# 4_PowerSupplie.net
KiCad netlist of a schematic drawn in Altium Designer
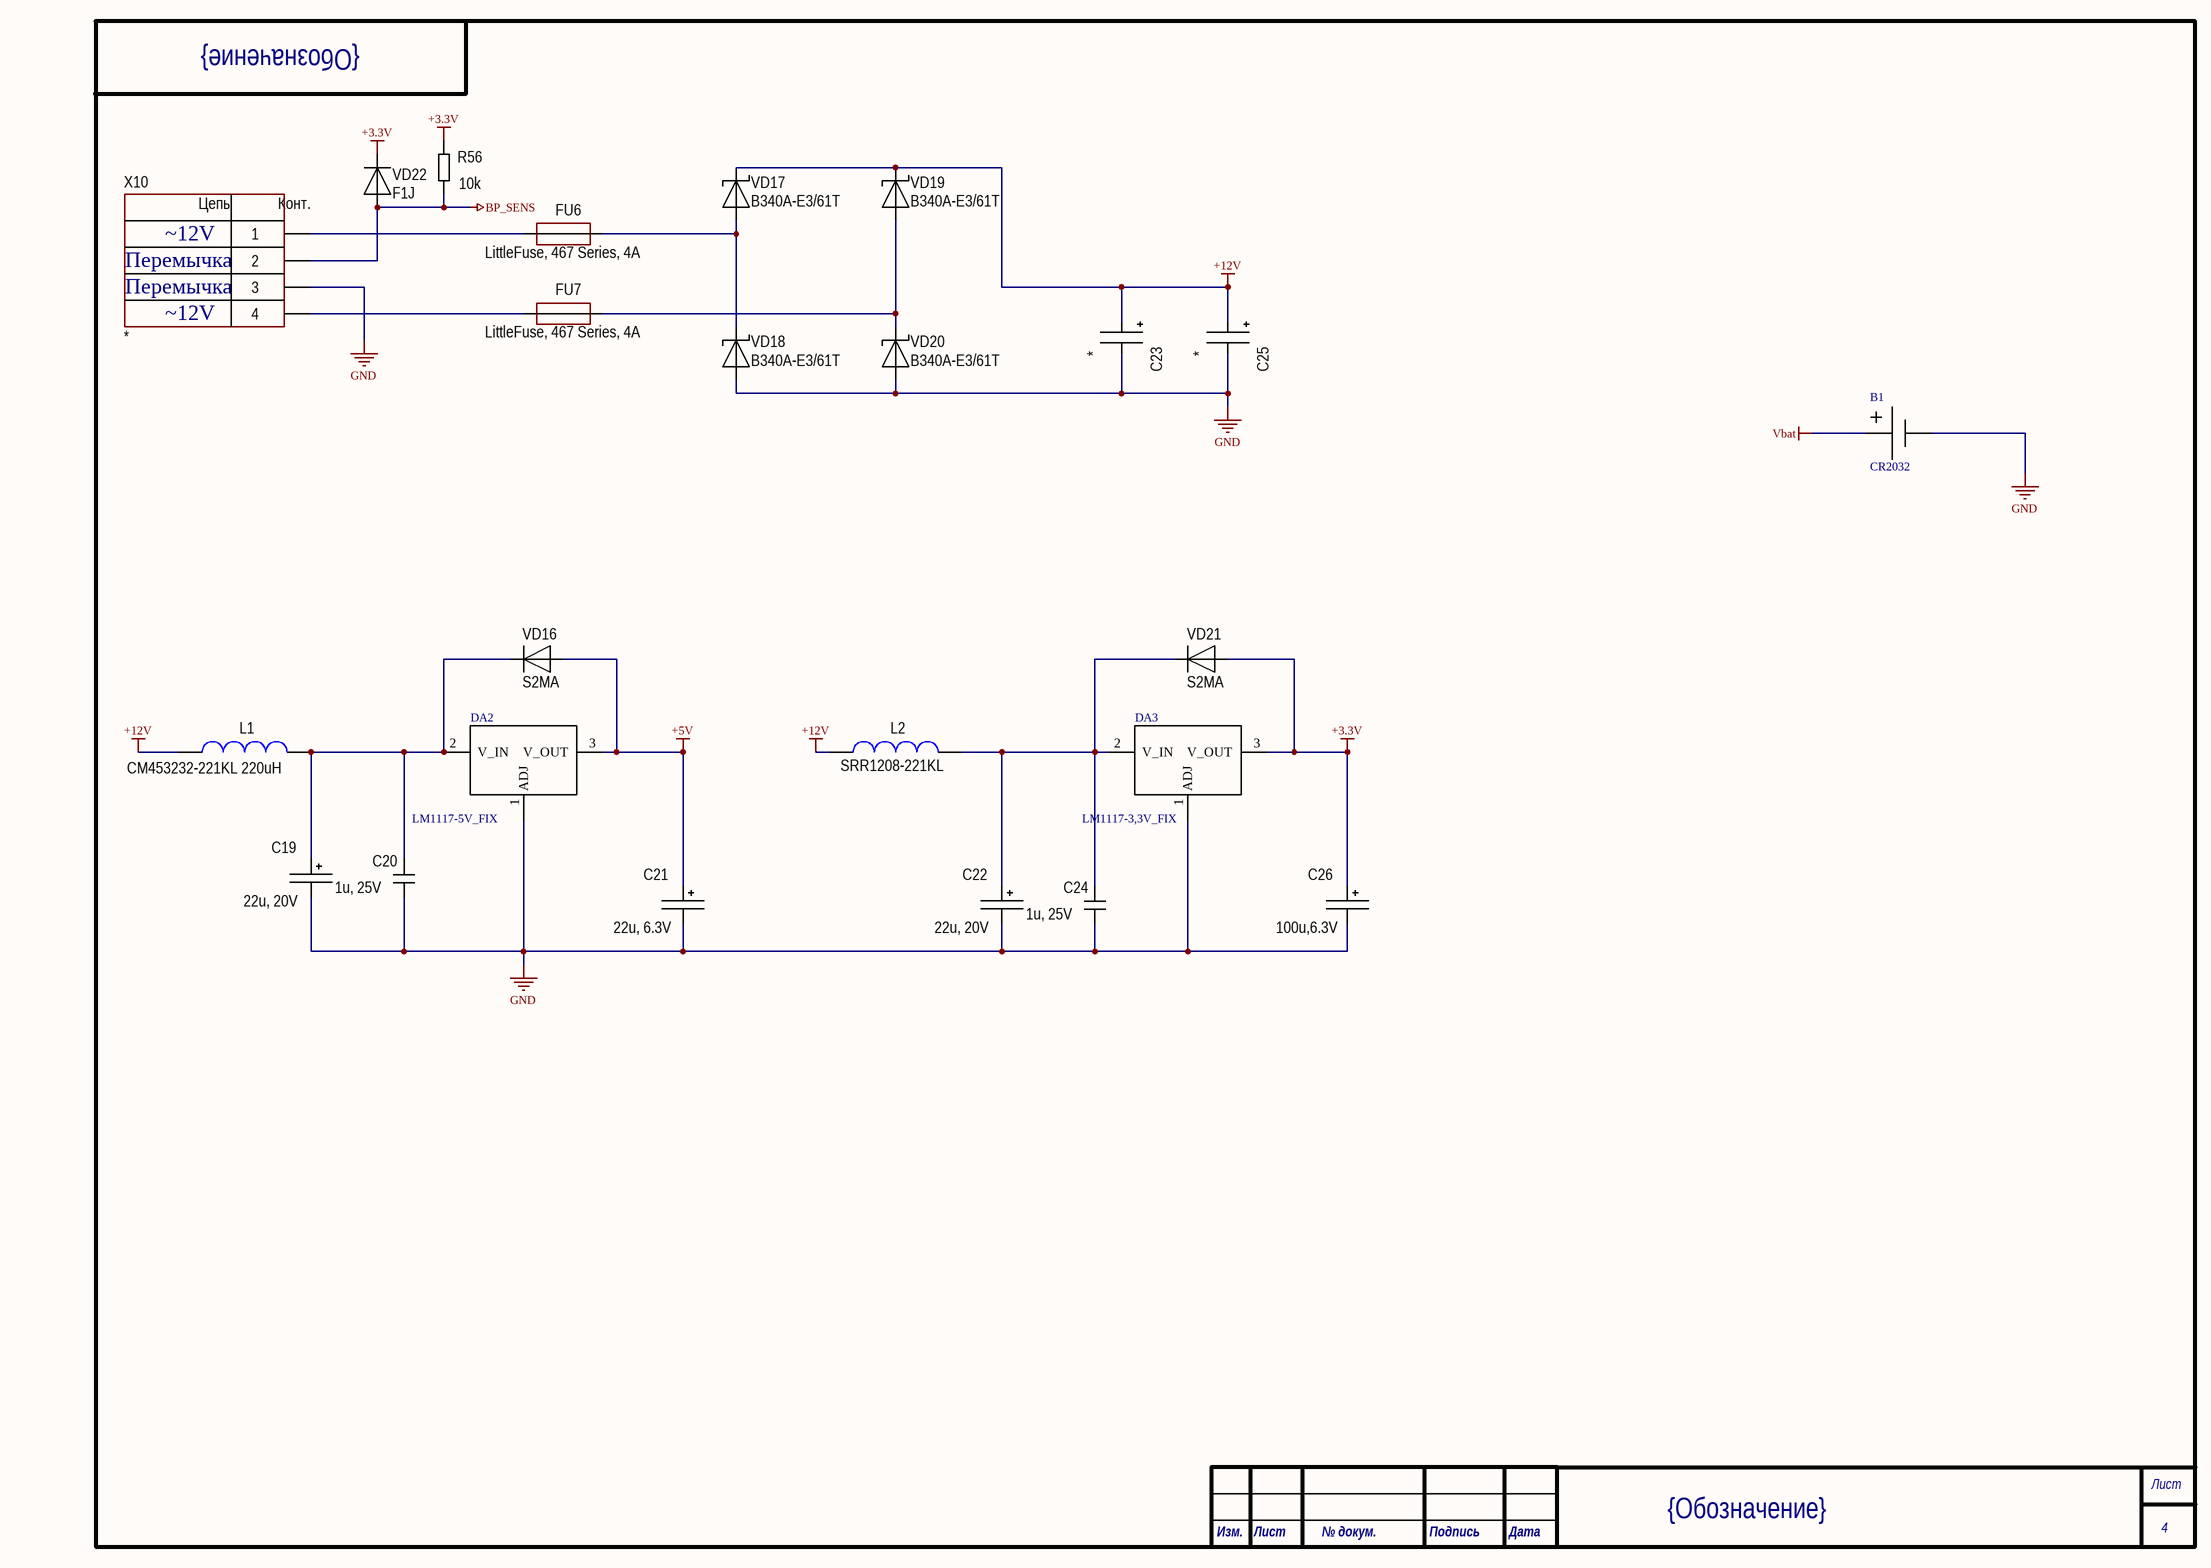
[diagram p0: 4_PowerSupplie.SchDoc]

(export (version "E")
  (design (tool "Eeschema 10.0.6"))
  (components
    (comp (ref "B1")
      (value "CR2032")
      (footprint "CR2032")
      (libsource (lib "Melochi") (part "Battery_CR2032"))
    )
    (comp (ref "C19")
      (value "22u, 20V")
      (footprint "TANTAL_B")
      (libsource (lib "Condensators") (part "TantalCap"))
    )
    (comp (ref "C20")
      (value "1u, 25V")
      (footprint "CH0805C")
      (libsource (lib "Condensators") (part "Capacitor"))
    )
    (comp (ref "C21")
      (value "22u, 6.3V")
      (footprint "TANTAL_B")
      (libsource (lib "Condensators") (part "TantalCap"))
    )
    (comp (ref "C22")
      (value "22u, 20V")
      (footprint "TANTAL_B")
      (libsource (lib "Condensators") (part "TantalCap"))
    )
    (comp (ref "C23") (value "*") (footprint "D10C4.4H10") (libsource (lib "Condensators") (part "AlumCap")))
    (comp (ref "C24")
      (value "1u, 25V")
      (footprint "CH0805C")
      (libsource (lib "Condensators") (part "Capacitor"))
    )
    (comp (ref "C25") (value "*") (footprint "D10C4.4H10") (libsource (lib "Condensators") (part "AlumCap")))
    (comp (ref "C26")
      (value "100u,6.3V")
      (footprint "TANTAL_B")
      (libsource (lib "Condensators") (part "TantalCap"))
    )
    (comp (ref "DA2")
      (value "LM1117-5V_FIX")
      (footprint "SOT223_123")
      (libsource (lib "MicroIC") (part "LM1117"))
    )
    (comp (ref "DA3")
      (value "LM1117-3,3V_FIX")
      (footprint "SOT223_123")
      (libsource (lib "MicroIC") (part "LM1117"))
    )
    (comp (ref "FU6")
      (value "LittleFuse, 467 Series, 4A")
      (footprint "CH0603F")
      (libsource (lib "Melochi") (part "Fuse"))
    )
    (comp (ref "FU7")
      (value "LittleFuse, 467 Series, 4A")
      (footprint "CH0603F")
      (libsource (lib "Melochi") (part "Fuse"))
    )
    (comp (ref "L1")
      (value "CM453232-221KL 220uH")
      (footprint "IND:1812")
      (libsource (lib "Inductance") (part "Inductor"))
    )
    (comp (ref "L2")
      (value "SRR1208-221KL")
      (footprint "IND: SRR1208")
      (libsource (lib "Inductance") (part "Inductor"))
    )
    (comp (ref "R56") (value "10k") (footprint "CH0805R") (libsource (lib "Resistors") (part "Resistor")))
    (comp (ref "VD16") (value "S2MA") (footprint "SMA") (libsource (lib "Diods") (part "Diod")))
    (comp (ref "VD17")
      (value "B340A-E3/61T")
      (footprint "SMA")
      (libsource (lib "Diods") (part "Diod Schottky"))
    )
    (comp (ref "VD18")
      (value "B340A-E3/61T")
      (footprint "SMA")
      (libsource (lib "Diods") (part "Diod Schottky"))
    )
    (comp (ref "VD19")
      (value "B340A-E3/61T")
      (footprint "SMA")
      (libsource (lib "Diods") (part "Diod Schottky"))
    )
    (comp (ref "VD20")
      (value "B340A-E3/61T")
      (footprint "SMA")
      (libsource (lib "Diods") (part "Diod Schottky"))
    )
    (comp (ref "VD21") (value "S2MA") (footprint "SMA") (libsource (lib "Diods") (part "Diod")))
    (comp (ref "VD22") (value "F1J") (footprint "SOD123F") (libsource (lib "Diods") (part "Diod")))
    (comp (ref "X10")
      (value "*")
      (footprint "CON: CWF-4")
      (libsource (lib "Connectors") (part "4-Connector"))
    )
  )
  (nets
    (net (code "1") (name "+3.3V") (class "Default")
      (node (ref "C26") (pin "1") (pinfunction "1_1") (pintype "power_in"))
      (node (ref "DA3") (pin "3") (pinfunction "V_OUT_3") (pintype "passive"))
      (node (ref "R56") (pin "2") (pinfunction "2_2") (pintype "passive"))
      (node (ref "VD21") (pin "1") (pinfunction "1_1") (pintype "passive"))
      (node (ref "VD22") (pin "2") (pinfunction "2_2") (pintype "passive"))
    )
    (net (code "2") (name "+5V") (class "Default")
      (node (ref "C21") (pin "1") (pinfunction "1_1") (pintype "power_in"))
      (node (ref "DA2") (pin "3") (pinfunction "V_OUT_3") (pintype "passive"))
      (node (ref "VD16") (pin "1") (pinfunction "1_1") (pintype "passive"))
    )
    (net (code "3") (name "+12V") (class "Default")
      (node (ref "C23") (pin "1") (pinfunction "1_1") (pintype "power_in"))
      (node (ref "C25") (pin "1") (pinfunction "1_1") (pintype "power_in"))
      (node (ref "L1") (pin "2") (pinfunction "2_2") (pintype "passive"))
      (node (ref "L2") (pin "2") (pinfunction "2_2") (pintype "passive"))
      (node (ref "VD17") (pin "2") (pinfunction "2_2") (pintype "passive"))
      (node (ref "VD19") (pin "2") (pinfunction "2_2") (pintype "passive"))
    )
    (net (code "4") (name "BP_SENS") (class "Default")
      (node (ref "R56") (pin "1") (pinfunction "1_1") (pintype "passive"))
      (node (ref "VD22") (pin "1") (pinfunction "1_1") (pintype "passive"))
      (node (ref "X10") (pin "2") (pinfunction "2_2") (pintype "passive"))
    )
    (net (code "5") (name "GND") (class "Default")
      (node (ref "B1") (pin "2") (pinfunction "2_2") (pintype "passive"))
      (node (ref "C19") (pin "2") (pinfunction "2_2") (pintype "power_in"))
      (node (ref "C20") (pin "1") (pinfunction "1_1") (pintype "passive"))
      (node (ref "C21") (pin "2") (pinfunction "2_2") (pintype "power_in"))
      (node (ref "C22") (pin "2") (pinfunction "2_2") (pintype "power_in"))
      (node (ref "C23") (pin "2") (pinfunction "2_2") (pintype "power_in"))
      (node (ref "C24") (pin "1") (pinfunction "1_1") (pintype "passive"))
      (node (ref "C25") (pin "2") (pinfunction "2_2") (pintype "power_in"))
      (node (ref "C26") (pin "2") (pinfunction "2_2") (pintype "power_in"))
      (node (ref "DA2") (pin "1") (pinfunction "ADJ_1") (pintype "passive"))
      (node (ref "DA3") (pin "1") (pinfunction "ADJ_1") (pintype "passive"))
      (node (ref "VD18") (pin "1") (pinfunction "1_1") (pintype "passive"))
      (node (ref "VD20") (pin "1") (pinfunction "1_1") (pintype "passive"))
      (node (ref "X10") (pin "3") (pinfunction "3_3") (pintype "power_in"))
    )
    (net (code "6") (name "Net-(DA2-V_IN)") (class "Default")
      (node (ref "C19") (pin "1") (pinfunction "1_1") (pintype "power_in"))
      (node (ref "C20") (pin "2") (pinfunction "2_2") (pintype "passive"))
      (node (ref "DA2") (pin "2") (pinfunction "V_IN_2") (pintype "passive"))
      (node (ref "L1") (pin "1") (pinfunction "1_1") (pintype "passive"))
      (node (ref "VD16") (pin "2") (pinfunction "2_2") (pintype "passive"))
    )
    (net (code "7") (name "Net-(DA3-V_IN)") (class "Default")
      (node (ref "C22") (pin "1") (pinfunction "1_1") (pintype "power_in"))
      (node (ref "C24") (pin "2") (pinfunction "2_2") (pintype "passive"))
      (node (ref "DA3") (pin "2") (pinfunction "V_IN_2") (pintype "passive"))
      (node (ref "L2") (pin "1") (pinfunction "1_1") (pintype "passive"))
      (node (ref "VD21") (pin "2") (pinfunction "2_2") (pintype "passive"))
    )
    (net (code "8") (name "Net-(FU6-Pad1)") (class "Default")
      (node (ref "FU6") (pin "1") (pinfunction "1_1") (pintype "passive"))
      (node (ref "X10") (pin "1") (pinfunction "1_1") (pintype "passive"))
    )
    (net (code "9") (name "Net-(FU6-Pad2)") (class "Default")
      (node (ref "FU6") (pin "2") (pinfunction "2_2") (pintype "passive"))
      (node (ref "VD17") (pin "1") (pinfunction "1_1") (pintype "passive"))
      (node (ref "VD18") (pin "2") (pinfunction "2_2") (pintype "passive"))
    )
    (net (code "10") (name "Net-(FU7-Pad1)") (class "Default")
      (node (ref "FU7") (pin "1") (pinfunction "1_1") (pintype "passive"))
      (node (ref "X10") (pin "4") (pinfunction "4_4") (pintype "power_in"))
    )
    (net (code "11") (name "Net-(FU7-Pad2)") (class "Default")
      (node (ref "FU7") (pin "2") (pinfunction "2_2") (pintype "passive"))
      (node (ref "VD19") (pin "1") (pinfunction "1_1") (pintype "passive"))
      (node (ref "VD20") (pin "2") (pinfunction "2_2") (pintype "passive"))
    )
    (net (code "12") (name "Vbat") (class "Default")
      (node (ref "B1") (pin "1") (pinfunction "1_1") (pintype "passive"))
    )
  )
)
